# PIC12F1822.net
KiCad netlist of a schematic drawn in EAGLE
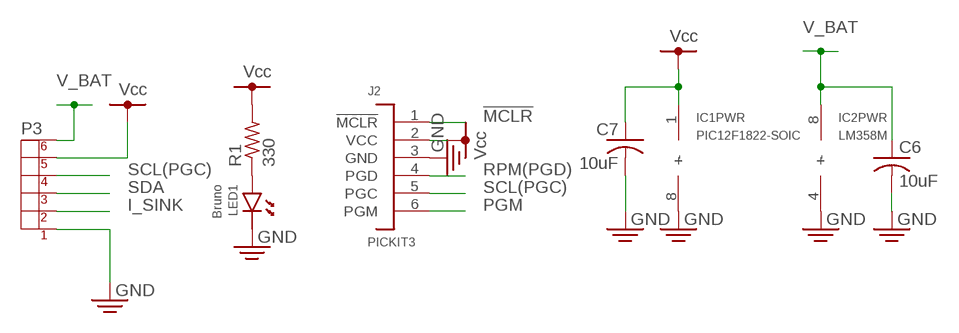
[diagram p0: schematic, sheet 1]
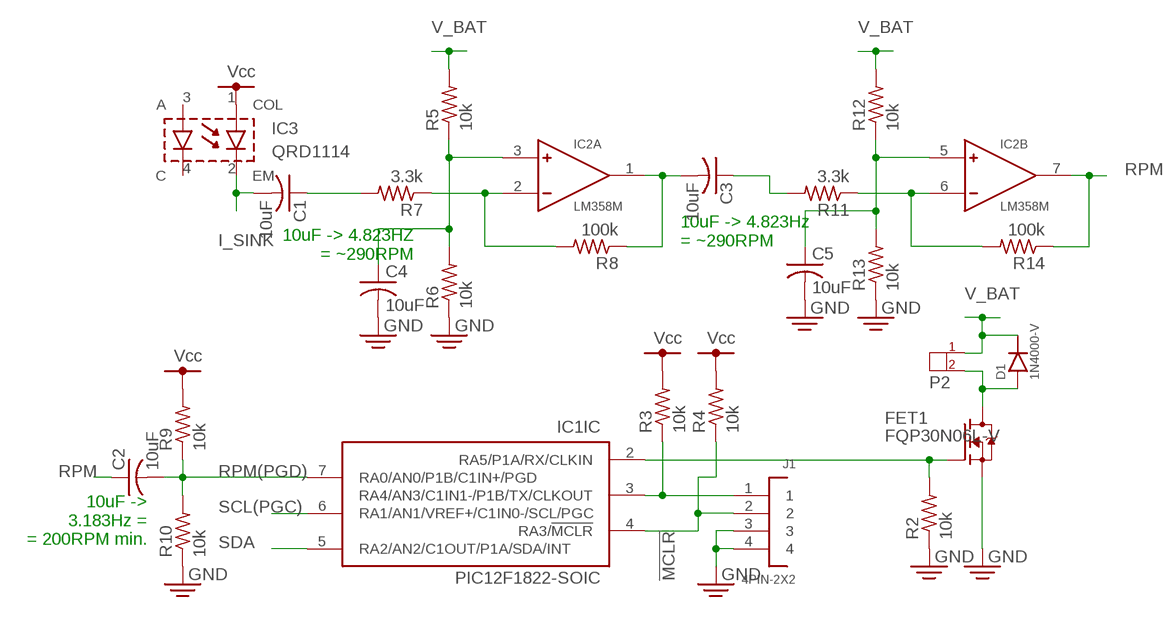
[diagram p1: schematic, sheet 2]

(export (version "E")
  (design (tool "Eeschema 10.0.6"))
  (components
    (comp (ref "C6")
      (value "10uF")
      (footprint "eagle-import:C0805")
      (libsource (lib "eagle-import") (part "C-USC0805"))
    )
    (comp (ref "C7")
      (value "10uF")
      (footprint "eagle-import:C0805")
      (libsource (lib "eagle-import") (part "C-USC0805"))
    )
    (comp (ref "IC1")
      (value "PIC12F1822-SOIC")
      (footprint "eagle-import:8-SOP")
      (libsource (lib "eagle-import") (part "PIC12F1822-SOIC"))
    )
    (comp (ref "IC2")
      (value "LM358M")
      (footprint "eagle-import:8-SOP")
      (libsource (lib "eagle-import") (part "LM358M"))
    )
    (comp (ref "J2")
      (value "PICKIT3")
      (footprint "eagle-import:PICKIT3")
      (libsource (lib "eagle-import") (part "PICKIT3"))
    )
    (comp (ref "LED1")
      (value "Bruno")
      (footprint "eagle-import:LED3MM")
      (libsource (lib "eagle-import") (part "LED3MM"))
    )
    (comp (ref "P3")
      (value "CONN-6P-PNI")
      (footprint "eagle-import:B06B-PNISK")
      (libsource (lib "eagle-import") (part "CONN-6P-PNI"))
    )
    (comp (ref "R1")
      (value "330")
      (footprint "eagle-import:R0805")
      (libsource (lib "eagle-import") (part "R-US_R0805"))
    )
    (comp (ref "C1")
      (value "10uF")
      (footprint "eagle-import:C0805")
      (libsource (lib "eagle-import") (part "C-USC0805"))
    )
    (comp (ref "C2")
      (value "10uF")
      (footprint "eagle-import:C0805")
      (libsource (lib "eagle-import") (part "C-USC0805"))
    )
    (comp (ref "C3")
      (value "10uF")
      (footprint "eagle-import:C0805")
      (libsource (lib "eagle-import") (part "C-USC0805"))
    )
    (comp (ref "C4")
      (value "10uF")
      (footprint "eagle-import:C0805")
      (libsource (lib "eagle-import") (part "C-USC0805"))
    )
    (comp (ref "C5")
      (value "10uF")
      (footprint "eagle-import:C0805")
      (libsource (lib "eagle-import") (part "C-USC0805"))
    )
    (comp (ref "D1")
      (value "1N4000-V")
      (footprint "eagle-import:DIODE-V")
      (libsource (lib "eagle-import") (part "1N4000-V"))
    )
    (comp (ref "FET1")
      (value "FQP30N06L-V")
      (footprint "eagle-import:TO220V")
      (libsource (lib "eagle-import") (part "FQP30N06L-V"))
    )
    (comp (ref "IC3")
      (value "QRD1114")
      (footprint "eagle-import:QRD1114")
      (libsource (lib "eagle-import") (part "QRD1114"))
    )
    (comp (ref "J1")
      (value "4PIN-2X2")
      (footprint "eagle-import:4P-2X2")
      (libsource (lib "eagle-import") (part "4PIN-2X2"))
    )
    (comp (ref "P2")
      (value "CONN-2P-PNI")
      (footprint "eagle-import:B02B-PNISK")
      (libsource (lib "eagle-import") (part "CONN-2P-PNI"))
    )
    (comp (ref "R2")
      (value "10k")
      (footprint "eagle-import:R0805")
      (libsource (lib "eagle-import") (part "R-US_R0805"))
    )
    (comp (ref "R3")
      (value "10k")
      (footprint "eagle-import:R0805")
      (libsource (lib "eagle-import") (part "R-US_R0805"))
    )
    (comp (ref "R4")
      (value "10k")
      (footprint "eagle-import:R0805")
      (libsource (lib "eagle-import") (part "R-US_R0805"))
    )
    (comp (ref "R5")
      (value "10k")
      (footprint "eagle-import:R0805")
      (libsource (lib "eagle-import") (part "R-US_R0805"))
    )
    (comp (ref "R6")
      (value "10k")
      (footprint "eagle-import:R0805")
      (libsource (lib "eagle-import") (part "R-US_R0805"))
    )
    (comp (ref "R7")
      (value "3.3k")
      (footprint "eagle-import:R0805")
      (libsource (lib "eagle-import") (part "R-US_R0805"))
    )
    (comp (ref "R8")
      (value "100k")
      (footprint "eagle-import:R0805")
      (libsource (lib "eagle-import") (part "R-US_R0805"))
    )
    (comp (ref "R9")
      (value "10k")
      (footprint "eagle-import:R0805")
      (libsource (lib "eagle-import") (part "R-US_R0805"))
    )
    (comp (ref "R10")
      (value "10k")
      (footprint "eagle-import:R0805")
      (libsource (lib "eagle-import") (part "R-US_R0805"))
    )
    (comp (ref "R11")
      (value "3.3k")
      (footprint "eagle-import:R0805")
      (libsource (lib "eagle-import") (part "R-US_R0805"))
    )
    (comp (ref "R12")
      (value "10k")
      (footprint "eagle-import:R0805")
      (libsource (lib "eagle-import") (part "R-US_R0805"))
    )
    (comp (ref "R13")
      (value "10k")
      (footprint "eagle-import:R0805")
      (libsource (lib "eagle-import") (part "R-US_R0805"))
    )
    (comp (ref "R14")
      (value "100k")
      (footprint "eagle-import:R0805")
      (libsource (lib "eagle-import") (part "R-US_R0805"))
    )
  )
  (nets
    (net (code "1") (name "GND") (class "Default")
      (node (ref "C4") (pin "2") (pinfunction "2_2") (pintype "passive"))
      (node (ref "C5") (pin "2") (pinfunction "2_2") (pintype "passive"))
      (node (ref "C6") (pin "2") (pinfunction "2_2") (pintype "passive"))
      (node (ref "C7") (pin "2") (pinfunction "2_2") (pintype "passive"))
      (node (ref "FET1") (pin "3") (pinfunction "S_3") (pintype "passive"))
      (node (ref "IC1") (pin "8") (pinfunction "-_8") (pintype "bidirectional"))
      (node (ref "IC2") (pin "4") (pinfunction "-_4") (pintype "bidirectional"))
      (node (ref "J1") (pin "3") (pinfunction "3_3") (pintype "bidirectional"))
      (node (ref "J1") (pin "4") (pinfunction "4_4") (pintype "bidirectional"))
      (node (ref "J2") (pin "3") (pinfunction "GND_3") (pintype "bidirectional"))
      (node (ref "LED1") (pin "C") (pinfunction "C_C") (pintype "bidirectional"))
      (node (ref "P3") (pin "1") (pinfunction "1_1") (pintype "bidirectional"))
      (node (ref "R10") (pin "1") (pinfunction "1_1") (pintype "passive"))
      (node (ref "R13") (pin "1") (pinfunction "1_1") (pintype "passive"))
      (node (ref "R2") (pin "1") (pinfunction "1_1") (pintype "passive"))
      (node (ref "R6") (pin "1") (pinfunction "1_1") (pintype "passive"))
    )
    (net (code "2") (name "I_SINK") (class "Default")
      (node (ref "C1") (pin "2") (pinfunction "2_2") (pintype "passive"))
      (node (ref "IC3") (pin "2") (pinfunction "EM_2") (pintype "bidirectional"))
      (node (ref "P3") (pin "2") (pinfunction "2_2") (pintype "bidirectional"))
    )
    (net (code "3") (name "Net-(C1-Pad1)") (class "Default")
      (node (ref "C1") (pin "1") (pinfunction "1_1") (pintype "passive"))
      (node (ref "R7") (pin "2") (pinfunction "2_2") (pintype "passive"))
    )
    (net (code "4") (name "Net-(C3-Pad1)") (class "Default")
      (node (ref "C3") (pin "1") (pinfunction "1_1") (pintype "passive"))
      (node (ref "R11") (pin "2") (pinfunction "2_2") (pintype "passive"))
    )
    (net (code "5") (name "Net-(FET1-D)") (class "Default")
      (node (ref "D1") (pin "A") (pinfunction "A_A") (pintype "bidirectional"))
      (node (ref "FET1") (pin "2") (pinfunction "D_2") (pintype "passive"))
      (node (ref "P2") (pin "2") (pinfunction "2_2") (pintype "bidirectional"))
    )
    (net (code "6") (name "Net-(FET1-G)") (class "Default")
      (node (ref "FET1") (pin "1") (pinfunction "G_1") (pintype "passive"))
      (node (ref "IC1") (pin "2") (pinfunction "RA5/P1A/RX/CLKIN_2") (pintype "bidirectional"))
      (node (ref "R2") (pin "2") (pinfunction "2_2") (pintype "passive"))
    )
    (net (code "7") (name "Net-(IC1A-RA4{slash}AN3{slash}C1IN1-{slash}P1B{slash}TX{slash}CLKOUT)") (class "Default")
      (node (ref "IC1") (pin "3") (pinfunction "RA4/AN3/C1IN1-/P1B/TX/CLKOUT_3") (pintype "bidirectional"))
      (node (ref "J1") (pin "1") (pinfunction "1_1") (pintype "bidirectional"))
      (node (ref "R3") (pin "1") (pinfunction "1_1") (pintype "passive"))
    )
    (net (code "8") (name "Net-(IC2A-+)") (class "Default")
      (node (ref "C4") (pin "1") (pinfunction "1_1") (pintype "passive"))
      (node (ref "IC2") (pin "3") (pinfunction "+_3") (pintype "bidirectional"))
      (node (ref "R5") (pin "1") (pinfunction "1_1") (pintype "passive"))
      (node (ref "R6") (pin "2") (pinfunction "2_2") (pintype "passive"))
    )
    (net (code "9") (name "Net-(IC2A--)") (class "Default")
      (node (ref "IC2") (pin "2") (pinfunction "-_2") (pintype "bidirectional"))
      (node (ref "R7") (pin "1") (pinfunction "1_1") (pintype "passive"))
      (node (ref "R8") (pin "2") (pinfunction "2_2") (pintype "passive"))
    )
    (net (code "10") (name "Net-(IC2A-OUT)") (class "Default")
      (node (ref "C3") (pin "2") (pinfunction "2_2") (pintype "passive"))
      (node (ref "IC2") (pin "1") (pinfunction "OUT_1") (pintype "bidirectional"))
      (node (ref "R8") (pin "1") (pinfunction "1_1") (pintype "passive"))
    )
    (net (code "11") (name "Net-(IC2B-+)") (class "Default")
      (node (ref "C5") (pin "1") (pinfunction "1_1") (pintype "passive"))
      (node (ref "IC2") (pin "5") (pinfunction "+_5") (pintype "bidirectional"))
      (node (ref "R12") (pin "1") (pinfunction "1_1") (pintype "passive"))
      (node (ref "R13") (pin "2") (pinfunction "2_2") (pintype "passive"))
    )
    (net (code "12") (name "Net-(IC2B--)") (class "Default")
      (node (ref "IC2") (pin "6") (pinfunction "-_6") (pintype "bidirectional"))
      (node (ref "R11") (pin "1") (pinfunction "1_1") (pintype "passive"))
      (node (ref "R14") (pin "2") (pinfunction "2_2") (pintype "passive"))
    )
    (net (code "13") (name "Net-(LED1-PadA)") (class "Default")
      (node (ref "LED1") (pin "A") (pinfunction "A_A") (pintype "bidirectional"))
      (node (ref "R1") (pin "1") (pinfunction "1_1") (pintype "passive"))
    )
    (net (code "14") (name "PGM") (class "Default")
      (node (ref "J2") (pin "6") (pinfunction "PGM_6") (pintype "bidirectional"))
    )
    (net (code "15") (name "RPM") (class "Default")
      (node (ref "C2") (pin "1") (pinfunction "1_1") (pintype "passive"))
      (node (ref "IC2") (pin "7") (pinfunction "OUT_7") (pintype "bidirectional"))
      (node (ref "R14") (pin "1") (pinfunction "1_1") (pintype "passive"))
    )
    (net (code "16") (name "RPM(PGD)") (class "Default")
      (node (ref "C2") (pin "2") (pinfunction "2_2") (pintype "passive"))
      (node (ref "IC1") (pin "7") (pinfunction "RA0/AN0/P1B/C1IN+/PGD_7") (pintype "bidirectional"))
      (node (ref "J2") (pin "4") (pinfunction "PGD_4") (pintype "bidirectional"))
      (node (ref "R10") (pin "2") (pinfunction "2_2") (pintype "passive"))
      (node (ref "R9") (pin "1") (pinfunction "1_1") (pintype "passive"))
    )
    (net (code "17") (name "SCL(PGC)") (class "Default")
      (node (ref "IC1") (pin "6") (pinfunction "RA1/AN1/VREF+/C1IN0-/SCL/PGC_6") (pintype "bidirectional"))
      (node (ref "J2") (pin "5") (pinfunction "PGC_5") (pintype "bidirectional"))
      (node (ref "P3") (pin "4") (pinfunction "4_4") (pintype "bidirectional"))
    )
    (net (code "18") (name "SDA") (class "Default")
      (node (ref "IC1") (pin "5") (pinfunction "RA2/AN2/C1OUT/P1A/SDA/INT_5") (pintype "bidirectional"))
      (node (ref "P3") (pin "3") (pinfunction "3_3") (pintype "bidirectional"))
    )
    (net (code "19") (name "VCC") (class "Default")
      (node (ref "C7") (pin "1") (pinfunction "1_1") (pintype "passive"))
      (node (ref "IC1") (pin "1") (pinfunction "+_1") (pintype "bidirectional"))
      (node (ref "IC3") (pin "1") (pinfunction "COL_1") (pintype "bidirectional"))
      (node (ref "J2") (pin "2") (pinfunction "VCC_2") (pintype "bidirectional"))
      (node (ref "P3") (pin "5") (pinfunction "5_5") (pintype "bidirectional"))
      (node (ref "R1") (pin "2") (pinfunction "2_2") (pintype "passive"))
      (node (ref "R3") (pin "2") (pinfunction "2_2") (pintype "passive"))
      (node (ref "R4") (pin "2") (pinfunction "2_2") (pintype "passive"))
      (node (ref "R9") (pin "2") (pinfunction "2_2") (pintype "passive"))
    )
    (net (code "20") (name "V_BAT") (class "Default")
      (node (ref "C6") (pin "1") (pinfunction "1_1") (pintype "passive"))
      (node (ref "D1") (pin "C") (pinfunction "C_C") (pintype "bidirectional"))
      (node (ref "IC2") (pin "8") (pinfunction "+_8") (pintype "bidirectional"))
      (node (ref "P2") (pin "1") (pinfunction "1_1") (pintype "bidirectional"))
      (node (ref "P3") (pin "6") (pinfunction "6_6") (pintype "bidirectional"))
      (node (ref "R12") (pin "2") (pinfunction "2_2") (pintype "passive"))
      (node (ref "R5") (pin "2") (pinfunction "2_2") (pintype "passive"))
    )
    (net (code "21") (name "unconnected-(IC3-A-Pad3)") (class "Default")
      (node (ref "IC3") (pin "3") (pinfunction "A_3") (pintype "bidirectional"))
    )
    (net (code "22") (name "unconnected-(IC3-C-Pad4)") (class "Default")
      (node (ref "IC3") (pin "4") (pinfunction "C_4") (pintype "bidirectional"))
    )
    (net (code "23") (name "~{MCLR}") (class "Default")
      (node (ref "IC1") (pin "4") (pinfunction "RA3/~{MCLR}_4") (pintype "bidirectional"))
      (node (ref "J1") (pin "2") (pinfunction "2_2") (pintype "bidirectional"))
      (node (ref "J2") (pin "1") (pinfunction "~{MCLR}_1") (pintype "bidirectional"))
      (node (ref "R4") (pin "1") (pinfunction "1_1") (pintype "passive"))
    )
  )
)
